# pH-meter-v1-3.net
KiCad netlist of a schematic drawn in EAGLE
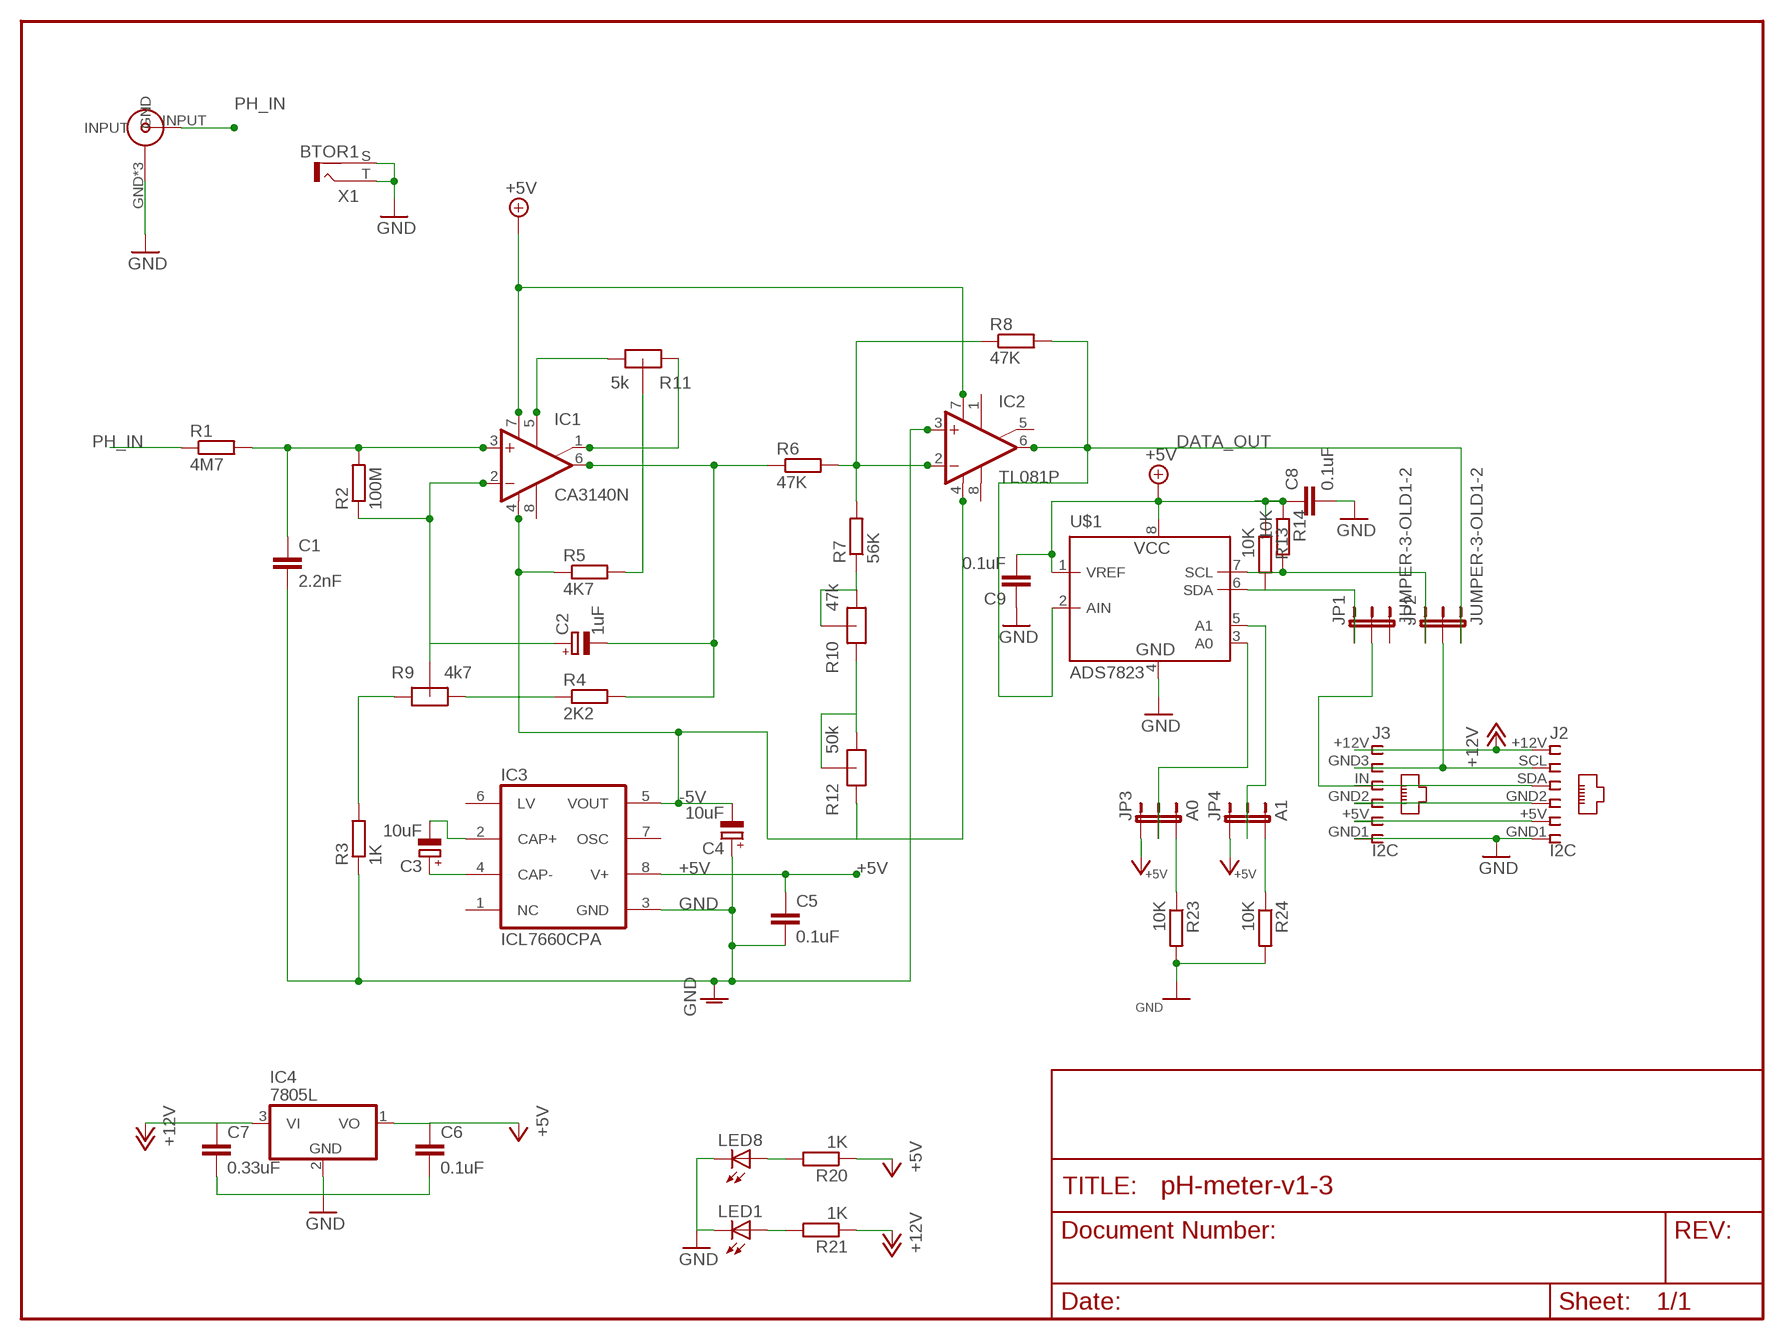
[diagram p0: schematic, sheet 1]

(export (version "E")
  (design (tool "Eeschema 10.0.6"))
  (components
    (comp (ref "C1")
      (value "2.2nF")
      (footprint "eagle-import:C025-030X050")
      (libsource (lib "eagle-import") (part "C-EU025-030X050"))
    )
    (comp (ref "C2")
      (value "1uF")
      (footprint "eagle-import:E2-4")
      (libsource (lib "eagle-import") (part "CPOL-EUE2-4"))
    )
    (comp (ref "C3")
      (value "10uF")
      (footprint "eagle-import:E2-4")
      (libsource (lib "eagle-import") (part "CPOL-EUE2-4"))
    )
    (comp (ref "C4")
      (value "10uF")
      (footprint "eagle-import:E2-4")
      (libsource (lib "eagle-import") (part "CPOL-EUE2-4"))
    )
    (comp (ref "C5")
      (value "0.1uF")
      (footprint "eagle-import:C025-030X050")
      (libsource (lib "eagle-import") (part "C-EU025-030X050"))
    )
    (comp (ref "C6")
      (value "0.1uF")
      (footprint "eagle-import:C025-030X050")
      (libsource (lib "eagle-import") (part "C-EU025-030X050"))
    )
    (comp (ref "C7")
      (value "0.33uF")
      (footprint "eagle-import:C025-030X050")
      (libsource (lib "eagle-import") (part "C-EU025-030X050"))
    )
    (comp (ref "C8")
      (value "0.1uF")
      (footprint "eagle-import:C025-030X050")
      (libsource (lib "eagle-import") (part "C-EU025-030X050"))
    )
    (comp (ref "C9")
      (value "0.1uF")
      (footprint "eagle-import:C025-030X050")
      (libsource (lib "eagle-import") (part "C-EU025-030X050"))
    )
    (comp (ref "IC1")
      (value "CA3140N")
      (footprint "eagle-import:DIL08")
      (libsource (lib "eagle-import") (part "CA3140N"))
    )
    (comp (ref "IC2")
      (value "TL081P")
      (footprint "eagle-import:DIL08")
      (libsource (lib "eagle-import") (part "TL081P"))
    )
    (comp (ref "IC3")
      (value "ICL7660CPA")
      (footprint "eagle-import:DIL08")
      (fields (field (name "MF") "INTERSIL"))
      (libsource (lib "eagle-import") (part "ICL7660CPA"))
    )
    (comp (ref "IC4")
      (value "7805L")
      (footprint "eagle-import:TO92")
      (libsource (lib "eagle-import") (part "78L05"))
    )
    (comp (ref "J2")
      (value "I2C")
      (footprint "eagle-import:RJ12-STRAIGHT-I2C")
      (libsource (lib "eagle-import") (part "RJ12STRAIGHT-I2C"))
    )
    (comp (ref "J3")
      (value "I2C")
      (footprint "eagle-import:RJ12-STRAIGHT-ANALOG")
      (libsource (lib "eagle-import") (part "RJ12STRAIGHT-ANALOG"))
    )
    (comp (ref "JP1")
      (value "JUMPER-3-OLD1-2")
      (footprint "eagle-import:SJ_3_PASTE1&2")
      (libsource (lib "eagle-import") (part "JUMPER-3-OLD1-2"))
    )
    (comp (ref "JP2")
      (value "JUMPER-3-OLD1-2")
      (footprint "eagle-import:SJ_3_PASTE1&2")
      (libsource (lib "eagle-import") (part "JUMPER-3-OLD1-2"))
    )
    (comp (ref "JP3")
      (value "A0")
      (footprint "eagle-import:SJ_3_PASTE1&2")
      (libsource (lib "eagle-import") (part "JUMPER-3-OLD1-2"))
    )
    (comp (ref "JP4")
      (value "A1")
      (footprint "eagle-import:SJ_3_PASTE1&2")
      (libsource (lib "eagle-import") (part "JUMPER-3-OLD1-2"))
    )
    (comp (ref "LED1")
      (value "LED3MM")
      (footprint "eagle-import:LED3MM")
      (libsource (lib "eagle-import") (part "LED3MM"))
    )
    (comp (ref "LED8")
      (value "LED3MM")
      (footprint "eagle-import:LED3MM")
      (libsource (lib "eagle-import") (part "LED3MM"))
    )
    (comp (ref "R1")
      (value "4M7")
      (footprint "eagle-import:0309_12")
      (libsource (lib "eagle-import") (part "R-EU_0309/12"))
    )
    (comp (ref "R2")
      (value "100M")
      (footprint "eagle-import:0309_12")
      (libsource (lib "eagle-import") (part "R-EU_0309/12"))
    )
    (comp (ref "R3")
      (value "1K")
      (footprint "eagle-import:0309_12")
      (libsource (lib "eagle-import") (part "R-EU_0309/12"))
    )
    (comp (ref "R4")
      (value "2K2")
      (footprint "eagle-import:0309_12")
      (libsource (lib "eagle-import") (part "R-EU_0309/12"))
    )
    (comp (ref "R5")
      (value "4K7")
      (footprint "eagle-import:0309_12")
      (libsource (lib "eagle-import") (part "R-EU_0309/12"))
    )
    (comp (ref "R6")
      (value "47K")
      (footprint "eagle-import:0309_12")
      (libsource (lib "eagle-import") (part "R-EU_0309/12"))
    )
    (comp (ref "R7")
      (value "56K")
      (footprint "eagle-import:0309_12")
      (libsource (lib "eagle-import") (part "R-EU_0309/12"))
    )
    (comp (ref "R8")
      (value "47K")
      (footprint "eagle-import:0309_12")
      (libsource (lib "eagle-import") (part "R-EU_0309/12"))
    )
    (comp (ref "R9")
      (value "4k7")
      (footprint "eagle-import:POT-METER_ALPS")
      (libsource (lib "eagle-import") (part "POT-METER_ALPS"))
    )
    (comp (ref "R10")
      (value "47k")
      (footprint "eagle-import:POT-METER_ALPS")
      (libsource (lib "eagle-import") (part "POT-METER_ALPS"))
    )
    (comp (ref "R11")
      (value "5k")
      (footprint "eagle-import:POT-METER_ALPS")
      (libsource (lib "eagle-import") (part "POT-METER_ALPS"))
    )
    (comp (ref "R12")
      (value "50k")
      (footprint "eagle-import:POT-METER_ALPS")
      (libsource (lib "eagle-import") (part "POT-METER_ALPS"))
    )
    (comp (ref "R13")
      (value "10K")
      (footprint "eagle-import:R1206")
      (libsource (lib "eagle-import") (part "R-EU_R1206"))
    )
    (comp (ref "R14")
      (value "10K")
      (footprint "eagle-import:R1206")
      (libsource (lib "eagle-import") (part "R-EU_R1206"))
    )
    (comp (ref "R20")
      (value "1K")
      (footprint "eagle-import:0309_12")
      (libsource (lib "eagle-import") (part "R-EU_0309/12"))
    )
    (comp (ref "R21")
      (value "1K")
      (footprint "eagle-import:0309_12")
      (libsource (lib "eagle-import") (part "R-EU_0309/12"))
    )
    (comp (ref "R23")
      (value "10K")
      (footprint "eagle-import:0309_12")
      (libsource (lib "eagle-import") (part "R-EU_0309/12"))
    )
    (comp (ref "R24")
      (value "10K")
      (footprint "eagle-import:0309_12")
      (libsource (lib "eagle-import") (part "R-EU_0309/12"))
    )
    (comp (ref "U$1")
      (value "ADS7823")
      (footprint "eagle-import:MSOP8")
      (libsource (lib "eagle-import") (part "ADS7823"))
    )
    (comp (ref "U$2")
      (value "BNC_IN")
      (footprint "eagle-import:BNC_VERTICAL_AMPHENOL")
      (libsource (lib "eagle-import") (part "BND_VERTICAL_AMPHENOL"))
    )
    (comp (ref "X1")
      (value "BTOR1")
      (footprint "eagle-import:BTOR1")
      (fields (field (name "MPN") "BTOR 1"))
      (libsource (lib "eagle-import") (part "BTOR1"))
    )
  )
  (nets
    (net (code "1") (name "+5V") (class "Default")
      (node (ref "C5") (pin "1") (pinfunction "1_1") (pintype "passive"))
      (node (ref "C6") (pin "1") (pinfunction "1_1") (pintype "passive"))
      (node (ref "C8") (pin "1") (pinfunction "1_1") (pintype "passive"))
      (node (ref "C9") (pin "2") (pinfunction "2_2") (pintype "passive"))
      (node (ref "IC1") (pin "7") (pinfunction "V+_7") (pintype "power_in"))
      (node (ref "IC2") (pin "7") (pinfunction "V+_7") (pintype "power_in"))
      (node (ref "IC3") (pin "8") (pinfunction "V+_8") (pintype "power_in"))
      (node (ref "IC4") (pin "1") (pinfunction "VO_1") (pintype "passive"))
      (node (ref "JP3") (pin "1") (pinfunction "1_1") (pintype "passive"))
      (node (ref "JP4") (pin "1") (pinfunction "1_1") (pintype "passive"))
      (node (ref "R13") (pin "1") (pinfunction "1_1") (pintype "passive"))
      (node (ref "R14") (pin "1") (pinfunction "1_1") (pintype "passive"))
      (node (ref "R20") (pin "1") (pinfunction "1_1") (pintype "passive"))
      (node (ref "U$1") (pin "1") (pinfunction "VREF_1") (pintype "input"))
      (node (ref "U$1") (pin "8") (pinfunction "VCC_8") (pintype "power_in"))
    )
    (net (code "2") (name "+12V") (class "Default")
      (node (ref "C7") (pin "1") (pinfunction "1_1") (pintype "passive"))
      (node (ref "IC4") (pin "3") (pinfunction "VI_3") (pintype "input"))
      (node (ref "J2") (pin "+12V") (pinfunction "1_+12V") (pintype "power_in"))
      (node (ref "J3") (pin "+12V") (pinfunction "1_+12V") (pintype "power_in"))
      (node (ref "R21") (pin "1") (pinfunction "1_1") (pintype "passive"))
    )
    (net (code "3") (name "/-5V") (class "Default")
      (node (ref "C4") (pin "-") (pinfunction "-_-") (pintype "passive"))
      (node (ref "IC1") (pin "4") (pinfunction "V-_4") (pintype "power_in"))
      (node (ref "IC2") (pin "4") (pinfunction "V-_4") (pintype "power_in"))
      (node (ref "IC3") (pin "5") (pinfunction "VOUT_5") (pintype "output"))
      (node (ref "R12") (pin "P$1") (pinfunction "IN_P$1") (pintype "bidirectional"))
      (node (ref "R5") (pin "1") (pinfunction "1_1") (pintype "passive"))
    )
    (net (code "4") (name "/DATA_OUT") (class "Default")
      (node (ref "IC2") (pin "6") (pinfunction "OUT_6") (pintype "output"))
      (node (ref "JP2") (pin "3") (pinfunction "3_3") (pintype "passive"))
      (node (ref "R8") (pin "2") (pinfunction "2_2") (pintype "passive"))
      (node (ref "U$1") (pin "2") (pinfunction "AIN_2") (pintype "input"))
    )
    (net (code "5") (name "/PH_IN") (class "Default")
      (node (ref "R1") (pin "1") (pinfunction "1_1") (pintype "passive"))
      (node (ref "U$2") (pin "INPUT") (pinfunction "INPUT_INPUT") (pintype "bidirectional"))
    )
    (net (code "6") (name "GND") (class "Default")
      (node (ref "C1") (pin "2") (pinfunction "2_2") (pintype "passive"))
      (node (ref "C4") (pin "+") (pinfunction "+_+") (pintype "passive"))
      (node (ref "C5") (pin "2") (pinfunction "2_2") (pintype "passive"))
      (node (ref "C6") (pin "2") (pinfunction "2_2") (pintype "passive"))
      (node (ref "C7") (pin "2") (pinfunction "2_2") (pintype "passive"))
      (node (ref "C8") (pin "2") (pinfunction "2_2") (pintype "passive"))
      (node (ref "C9") (pin "1") (pinfunction "1_1") (pintype "passive"))
      (node (ref "IC2") (pin "3") (pinfunction "+IN_3") (pintype "input"))
      (node (ref "IC3") (pin "3") (pinfunction "GND_3") (pintype "power_in"))
      (node (ref "IC4") (pin "2") (pinfunction "GND_2") (pintype "passive"))
      (node (ref "J2") (pin "GND1") (pinfunction "6_GND1") (pintype "power_in"))
      (node (ref "J2") (pin "GND2") (pinfunction "4_GND2") (pintype "power_in"))
      (node (ref "J3") (pin "GND1") (pinfunction "6_GND1") (pintype "power_in"))
      (node (ref "J3") (pin "GND2") (pinfunction "4_GND2") (pintype "power_in"))
      (node (ref "LED1") (pin "K") (pinfunction "C_K") (pintype "passive"))
      (node (ref "LED8") (pin "K") (pinfunction "C_K") (pintype "passive"))
      (node (ref "R23") (pin "2") (pinfunction "2_2") (pintype "passive"))
      (node (ref "R24") (pin "2") (pinfunction "2_2") (pintype "passive"))
      (node (ref "R3") (pin "1") (pinfunction "1_1") (pintype "passive"))
      (node (ref "U$1") (pin "4") (pinfunction "GND_4") (pintype "power_in"))
      (node (ref "U$2") (pin "GND") (pinfunction "GND_GND") (pintype "bidirectional"))
      (node (ref "U$2") (pin "GND_1") (pinfunction "GND_GND_1") (pintype "bidirectional"))
      (node (ref "U$2") (pin "GND_2") (pinfunction "GND_GND_2") (pintype "bidirectional"))
      (node (ref "X1") (pin "S") (pinfunction "2_S") (pintype "passive"))
      (node (ref "X1") (pin "T") (pinfunction "1_T") (pintype "passive"))
    )
    (net (code "7") (name "Net-(IC1-+IN)") (class "Default")
      (node (ref "C1") (pin "1") (pinfunction "1_1") (pintype "passive"))
      (node (ref "IC1") (pin "3") (pinfunction "+IN_3") (pintype "input"))
      (node (ref "R1") (pin "2") (pinfunction "2_2") (pintype "passive"))
      (node (ref "R2") (pin "2") (pinfunction "2_2") (pintype "passive"))
    )
    (net (code "8") (name "Net-(IC1--IN)") (class "Default")
      (node (ref "C2") (pin "+") (pinfunction "+_+") (pintype "passive"))
      (node (ref "IC1") (pin "2") (pinfunction "-IN_2") (pintype "input"))
      (node (ref "R2") (pin "1") (pinfunction "1_1") (pintype "passive"))
      (node (ref "R9") (pin "P$2") (pinfunction "DRIVE_P$2") (pintype "bidirectional"))
    )
    (net (code "9") (name "Net-(IC1-ON)") (class "Default")
      (node (ref "IC1") (pin "5") (pinfunction "ON_5") (pintype "passive"))
      (node (ref "R11") (pin "P$3") (pinfunction "OUT_P$3") (pintype "bidirectional"))
    )
    (net (code "10") (name "Net-(IC1-ON{slash}CMP)") (class "Default")
      (node (ref "IC1") (pin "1") (pinfunction "ON/CMP_1") (pintype "passive"))
      (node (ref "R11") (pin "P$1") (pinfunction "IN_P$1") (pintype "bidirectional"))
    )
    (net (code "11") (name "Net-(IC1-OUT)") (class "Default")
      (node (ref "C2") (pin "-") (pinfunction "-_-") (pintype "passive"))
      (node (ref "IC1") (pin "6") (pinfunction "OUT_6") (pintype "output"))
      (node (ref "R4") (pin "2") (pinfunction "2_2") (pintype "passive"))
      (node (ref "R6") (pin "1") (pinfunction "1_1") (pintype "passive"))
    )
    (net (code "12") (name "Net-(IC2--IN)") (class "Default")
      (node (ref "IC2") (pin "2") (pinfunction "-IN_2") (pintype "input"))
      (node (ref "R6") (pin "2") (pinfunction "2_2") (pintype "passive"))
      (node (ref "R7") (pin "2") (pinfunction "2_2") (pintype "passive"))
      (node (ref "R8") (pin "1") (pinfunction "1_1") (pintype "passive"))
    )
    (net (code "13") (name "Net-(IC3-CAP+)") (class "Default")
      (node (ref "C3") (pin "-") (pinfunction "-_-") (pintype "passive"))
      (node (ref "IC3") (pin "2") (pinfunction "CAP+_2") (pintype "passive"))
    )
    (net (code "14") (name "Net-(IC3-CAP-)") (class "Default")
      (node (ref "C3") (pin "+") (pinfunction "+_+") (pintype "passive"))
      (node (ref "IC3") (pin "4") (pinfunction "CAP-_4") (pintype "passive"))
    )
    (net (code "15") (name "Net-(J2-2)") (class "Default")
      (node (ref "J2") (pin "SCL") (pinfunction "2_SCL") (pintype "bidirectional"))
      (node (ref "J3") (pin "GND3") (pinfunction "2_GND3") (pintype "bidirectional"))
      (node (ref "JP2") (pin "2") (pinfunction "2_2") (pintype "passive"))
    )
    (net (code "16") (name "Net-(J2-3)") (class "Default")
      (node (ref "J2") (pin "SDA") (pinfunction "3_SDA") (pintype "bidirectional"))
      (node (ref "J3") (pin "IN") (pinfunction "3_IN") (pintype "bidirectional"))
      (node (ref "JP1") (pin "2") (pinfunction "2_2") (pintype "passive"))
    )
    (net (code "17") (name "Net-(J2-5)") (class "Default")
      (node (ref "J2") (pin "+5V") (pinfunction "5_+5V") (pintype "power_in"))
      (node (ref "J3") (pin "+5V") (pinfunction "5_+5V") (pintype "power_in"))
    )
    (net (code "18") (name "Net-(JP3-Pad3)") (class "Default")
      (node (ref "JP3") (pin "3") (pinfunction "3_3") (pintype "passive"))
      (node (ref "R23") (pin "1") (pinfunction "1_1") (pintype "passive"))
    )
    (net (code "19") (name "Net-(JP4-Pad3)") (class "Default")
      (node (ref "JP4") (pin "3") (pinfunction "3_3") (pintype "passive"))
      (node (ref "R24") (pin "1") (pinfunction "1_1") (pintype "passive"))
    )
    (net (code "20") (name "Net-(LED1-PadA)") (class "Default")
      (node (ref "LED1") (pin "A") (pinfunction "A_A") (pintype "passive"))
      (node (ref "R21") (pin "2") (pinfunction "2_2") (pintype "passive"))
    )
    (net (code "21") (name "Net-(LED8-PadA)") (class "Default")
      (node (ref "LED8") (pin "A") (pinfunction "A_A") (pintype "passive"))
      (node (ref "R20") (pin "2") (pinfunction "2_2") (pintype "passive"))
    )
    (net (code "22") (name "Net-(R9-IN)") (class "Default")
      (node (ref "R3") (pin "2") (pinfunction "2_2") (pintype "passive"))
      (node (ref "R9") (pin "P$1") (pinfunction "IN_P$1") (pintype "bidirectional"))
    )
    (net (code "23") (name "Net-(R9-OUT)") (class "Default")
      (node (ref "R4") (pin "1") (pinfunction "1_1") (pintype "passive"))
      (node (ref "R9") (pin "P$3") (pinfunction "OUT_P$3") (pintype "bidirectional"))
    )
    (net (code "24") (name "Net-(R10-DRIVE)") (class "Default")
      (node (ref "R10") (pin "P$2") (pinfunction "DRIVE_P$2") (pintype "bidirectional"))
      (node (ref "R10") (pin "P$3") (pinfunction "OUT_P$3") (pintype "bidirectional"))
      (node (ref "R7") (pin "1") (pinfunction "1_1") (pintype "passive"))
    )
    (net (code "25") (name "Net-(R10-IN)") (class "Default")
      (node (ref "R10") (pin "P$1") (pinfunction "IN_P$1") (pintype "bidirectional"))
      (node (ref "R12") (pin "P$2") (pinfunction "DRIVE_P$2") (pintype "bidirectional"))
      (node (ref "R12") (pin "P$3") (pinfunction "OUT_P$3") (pintype "bidirectional"))
    )
    (net (code "26") (name "Net-(R11-DRIVE)") (class "Default")
      (node (ref "R11") (pin "P$2") (pinfunction "DRIVE_P$2") (pintype "bidirectional"))
      (node (ref "R5") (pin "2") (pinfunction "2_2") (pintype "passive"))
    )
    (net (code "27") (name "Net-(U$1-A0)") (class "Default")
      (node (ref "JP3") (pin "2") (pinfunction "2_2") (pintype "passive"))
      (node (ref "U$1") (pin "3") (pinfunction "A0_3") (pintype "input"))
    )
    (net (code "28") (name "Net-(U$1-A1)") (class "Default")
      (node (ref "JP4") (pin "2") (pinfunction "2_2") (pintype "passive"))
      (node (ref "U$1") (pin "5") (pinfunction "A1_5") (pintype "input"))
    )
    (net (code "29") (name "Net-(U$1-SCL)") (class "Default")
      (node (ref "JP2") (pin "1") (pinfunction "1_1") (pintype "passive"))
      (node (ref "R14") (pin "2") (pinfunction "2_2") (pintype "passive"))
      (node (ref "U$1") (pin "7") (pinfunction "SCL_7") (pintype "input"))
    )
    (net (code "30") (name "Net-(U$1-SDA)") (class "Default")
      (node (ref "JP1") (pin "1") (pinfunction "1_1") (pintype "passive"))
      (node (ref "R13") (pin "2") (pinfunction "2_2") (pintype "passive"))
      (node (ref "U$1") (pin "6") (pinfunction "SDA_6") (pintype "bidirectional"))
    )
    (net (code "31") (name "unconnected-(IC1-CMP-Pad8)") (class "Default")
      (node (ref "IC1") (pin "8") (pinfunction "CMP_8") (pintype "passive"))
    )
    (net (code "32") (name "unconnected-(IC2-ON1-Pad1)") (class "Default")
      (node (ref "IC2") (pin "1") (pinfunction "ON1_1") (pintype "passive"))
    )
    (net (code "33") (name "unconnected-(IC2-ON2-Pad5)") (class "Default")
      (node (ref "IC2") (pin "5") (pinfunction "ON2_5") (pintype "passive"))
    )
    (net (code "34") (name "unconnected-(IC2-OPT-Pad8)") (class "Default")
      (node (ref "IC2") (pin "8") (pinfunction "OPT_8") (pintype "passive"))
    )
    (net (code "35") (name "unconnected-(IC3-LV-Pad6)") (class "Default")
      (node (ref "IC3") (pin "6") (pinfunction "LV_6") (pintype "passive"))
    )
    (net (code "36") (name "unconnected-(IC3-NC-Pad1)") (class "Default")
      (node (ref "IC3") (pin "1") (pinfunction "NC_1") (pintype "no_connect"))
    )
    (net (code "37") (name "unconnected-(IC3-OSC-Pad7)") (class "Default")
      (node (ref "IC3") (pin "7") (pinfunction "OSC_7") (pintype "output"))
    )
    (net (code "38") (name "unconnected-(JP1-Pad3)") (class "Default")
      (node (ref "JP1") (pin "3") (pinfunction "3_3") (pintype "passive"))
    )
    (net (code "39") (name "unconnected-(X1-2-PadS@1)") (class "Default")
      (node (ref "X1") (pin "S@1") (pinfunction "2_S@1") (pintype "passive"))
    )
    (net (code "40") (name "unconnected-(X1-2-PadS@2)") (class "Default")
      (node (ref "X1") (pin "S@2") (pinfunction "2_S@2") (pintype "passive"))
    )
    (net (code "41") (name "unconnected-(X1-2-PadS@3)") (class "Default")
      (node (ref "X1") (pin "S@3") (pinfunction "2_S@3") (pintype "passive"))
    )
  )
)
